# Daughter_Card_Connectors.net
KiCad netlist of a schematic drawn in Altium Designer
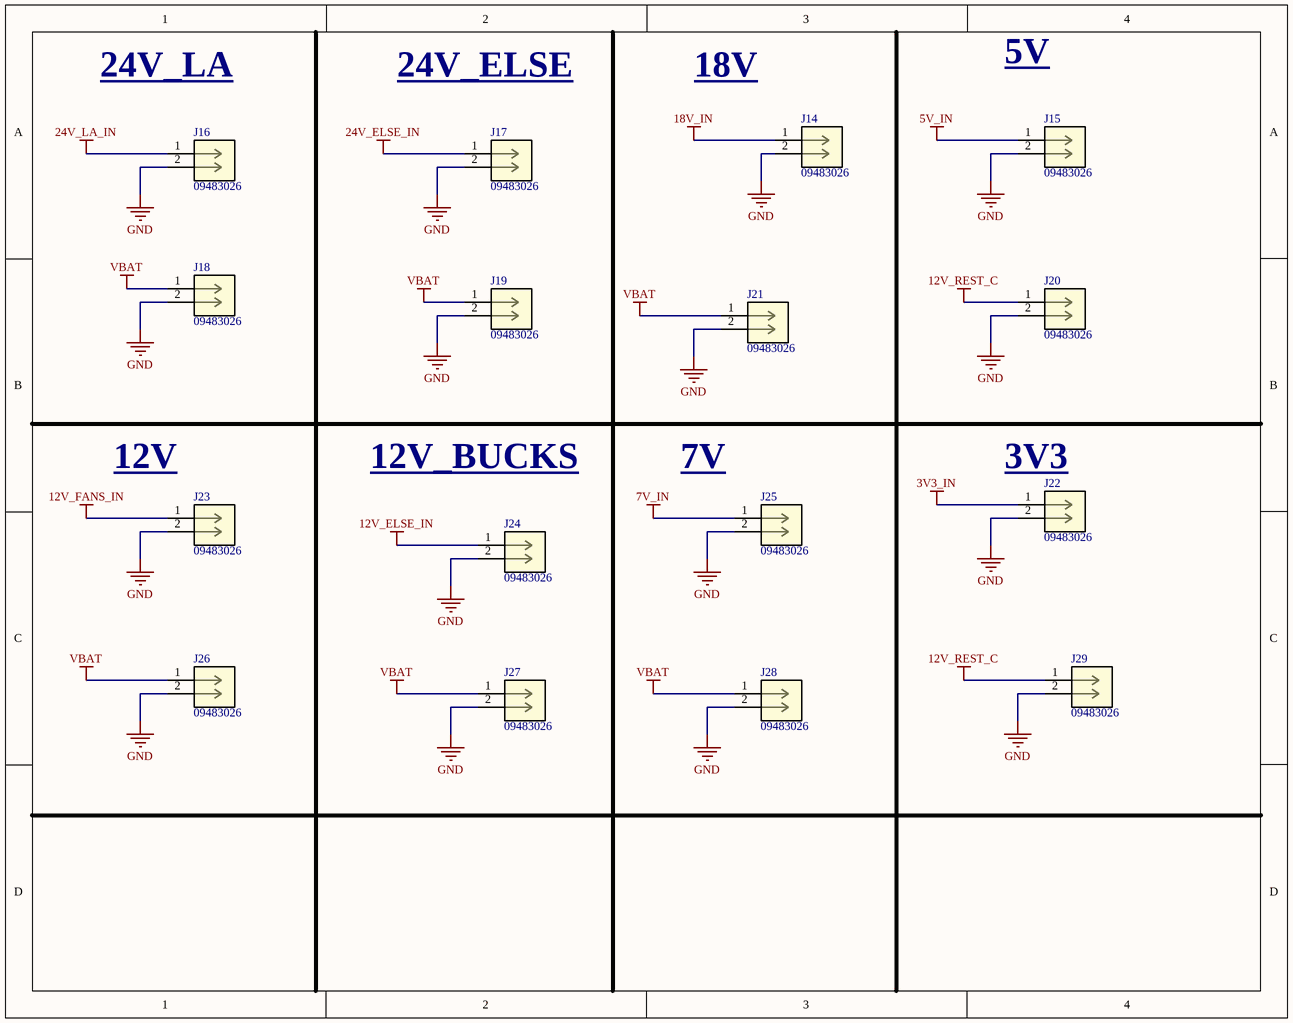
[diagram p0: Daughter_Card_Connectors.SchDoc]

(export (version "E")
  (design (tool "Eeschema 10.0.6"))
  (components
    (comp (ref "J14")
      (value "09483026")
      (footprint "CONN_SDA-41815_02_TE_H_MOL")
      (description "KK 396 PC Board Connector, Top Entry, Polyester Connector, Gold (Au) Selective, 2 Circuits")
      (fields (field (name "COPYRIGHT") "Copyright (C) 2025 Ultra Librarian. All rights reserved."))
      (libsource (lib "MasterLib") (part "CONN-2PIN-0009"))
    )
    (comp (ref "J15")
      (value "09483026")
      (footprint "CONN_SDA-41815_02_TE_H_MOL")
      (description "KK 396 PC Board Connector, Top Entry, Polyester Connector, Gold (Au) Selective, 2 Circuits")
      (fields (field (name "COPYRIGHT") "Copyright (C) 2025 Ultra Librarian. All rights reserved."))
      (libsource (lib "MasterLib") (part "CONN-2PIN-0009"))
    )
    (comp (ref "J16")
      (value "09483026")
      (footprint "CONN_SDA-41815_02_TE_H_MOL")
      (description "KK 396 PC Board Connector, Top Entry, Polyester Connector, Gold (Au) Selective, 2 Circuits")
      (fields (field (name "COPYRIGHT") "Copyright (C) 2025 Ultra Librarian. All rights reserved."))
      (libsource (lib "MasterLib") (part "CONN-2PIN-0009"))
    )
    (comp (ref "J17")
      (value "09483026")
      (footprint "CONN_SDA-41815_02_TE_H_MOL")
      (description "KK 396 PC Board Connector, Top Entry, Polyester Connector, Gold (Au) Selective, 2 Circuits")
      (fields (field (name "COPYRIGHT") "Copyright (C) 2025 Ultra Librarian. All rights reserved."))
      (libsource (lib "MasterLib") (part "CONN-2PIN-0009"))
    )
    (comp (ref "J18")
      (value "09483026")
      (footprint "CONN_SDA-41815_02_TE_H_MOL")
      (description "KK 396 PC Board Connector, Top Entry, Polyester Connector, Gold (Au) Selective, 2 Circuits")
      (fields (field (name "COPYRIGHT") "Copyright (C) 2025 Ultra Librarian. All rights reserved."))
      (libsource (lib "MasterLib") (part "CONN-2PIN-0009"))
    )
    (comp (ref "J19")
      (value "09483026")
      (footprint "CONN_SDA-41815_02_TE_H_MOL")
      (description "KK 396 PC Board Connector, Top Entry, Polyester Connector, Gold (Au) Selective, 2 Circuits")
      (fields (field (name "COPYRIGHT") "Copyright (C) 2025 Ultra Librarian. All rights reserved."))
      (libsource (lib "MasterLib") (part "CONN-2PIN-0009"))
    )
    (comp (ref "J20")
      (value "09483026")
      (footprint "CONN_SDA-41815_02_TE_H_MOL")
      (description "KK 396 PC Board Connector, Top Entry, Polyester Connector, Gold (Au) Selective, 2 Circuits")
      (fields (field (name "COPYRIGHT") "Copyright (C) 2025 Ultra Librarian. All rights reserved."))
      (libsource (lib "MasterLib") (part "CONN-2PIN-0009"))
    )
    (comp (ref "J21")
      (value "09483026")
      (footprint "CONN_SDA-41815_02_TE_H_MOL")
      (description "KK 396 PC Board Connector, Top Entry, Polyester Connector, Gold (Au) Selective, 2 Circuits")
      (fields (field (name "COPYRIGHT") "Copyright (C) 2025 Ultra Librarian. All rights reserved."))
      (libsource (lib "MasterLib") (part "CONN-2PIN-0009"))
    )
    (comp (ref "J22")
      (value "09483026")
      (footprint "CONN_SDA-41815_02_TE_H_MOL")
      (description "KK 396 PC Board Connector, Top Entry, Polyester Connector, Gold (Au) Selective, 2 Circuits")
      (fields (field (name "COPYRIGHT") "Copyright (C) 2025 Ultra Librarian. All rights reserved."))
      (libsource (lib "MasterLib") (part "CONN-2PIN-0009"))
    )
    (comp (ref "J23")
      (value "09483026")
      (footprint "CONN_SDA-41815_02_TE_H_MOL")
      (description "KK 396 PC Board Connector, Top Entry, Polyester Connector, Gold (Au) Selective, 2 Circuits")
      (fields (field (name "COPYRIGHT") "Copyright (C) 2025 Ultra Librarian. All rights reserved."))
      (libsource (lib "MasterLib") (part "CONN-2PIN-0009"))
    )
    (comp (ref "J24")
      (value "09483026")
      (footprint "CONN_SDA-41815_02_TE_H_MOL")
      (description "KK 396 PC Board Connector, Top Entry, Polyester Connector, Gold (Au) Selective, 2 Circuits")
      (fields (field (name "COPYRIGHT") "Copyright (C) 2025 Ultra Librarian. All rights reserved."))
      (libsource (lib "MasterLib") (part "CONN-2PIN-0009"))
    )
    (comp (ref "J25")
      (value "09483026")
      (footprint "CONN_SDA-41815_02_TE_H_MOL")
      (description "KK 396 PC Board Connector, Top Entry, Polyester Connector, Gold (Au) Selective, 2 Circuits")
      (fields (field (name "COPYRIGHT") "Copyright (C) 2025 Ultra Librarian. All rights reserved."))
      (libsource (lib "MasterLib") (part "CONN-2PIN-0009"))
    )
    (comp (ref "J26")
      (value "09483026")
      (footprint "CONN_SDA-41815_02_TE_H_MOL")
      (description "KK 396 PC Board Connector, Top Entry, Polyester Connector, Gold (Au) Selective, 2 Circuits")
      (fields (field (name "COPYRIGHT") "Copyright (C) 2025 Ultra Librarian. All rights reserved."))
      (libsource (lib "MasterLib") (part "CONN-2PIN-0009"))
    )
    (comp (ref "J27")
      (value "09483026")
      (footprint "CONN_SDA-41815_02_TE_H_MOL")
      (description "KK 396 PC Board Connector, Top Entry, Polyester Connector, Gold (Au) Selective, 2 Circuits")
      (fields (field (name "COPYRIGHT") "Copyright (C) 2025 Ultra Librarian. All rights reserved."))
      (libsource (lib "MasterLib") (part "CONN-2PIN-0009"))
    )
    (comp (ref "J28")
      (value "09483026")
      (footprint "CONN_SDA-41815_02_TE_H_MOL")
      (description "KK 396 PC Board Connector, Top Entry, Polyester Connector, Gold (Au) Selective, 2 Circuits")
      (fields (field (name "COPYRIGHT") "Copyright (C) 2025 Ultra Librarian. All rights reserved."))
      (libsource (lib "MasterLib") (part "CONN-2PIN-0009"))
    )
    (comp (ref "J29")
      (value "09483026")
      (footprint "CONN_SDA-41815_02_TE_H_MOL")
      (description "KK 396 PC Board Connector, Top Entry, Polyester Connector, Gold (Au) Selective, 2 Circuits")
      (fields (field (name "COPYRIGHT") "Copyright (C) 2025 Ultra Librarian. All rights reserved."))
      (libsource (lib "MasterLib") (part "CONN-2PIN-0009"))
    )
  )
  (nets
    (net (code "1") (name "3V3_IN") (class "Default")
      (node (ref "J22") (pin "1") (pinfunction "1_1") (pintype "passive"))
    )
    (net (code "2") (name "5V_IN") (class "Default")
      (node (ref "J15") (pin "1") (pinfunction "1_1") (pintype "passive"))
    )
    (net (code "3") (name "7V_IN") (class "Default")
      (node (ref "J25") (pin "1") (pinfunction "1_1") (pintype "passive"))
    )
    (net (code "4") (name "12V_ELSE_IN") (class "Default")
      (node (ref "J24") (pin "1") (pinfunction "1_1") (pintype "passive"))
    )
    (net (code "5") (name "12V_FANS_IN") (class "Default")
      (node (ref "J23") (pin "1") (pinfunction "1_1") (pintype "passive"))
    )
    (net (code "6") (name "12V_REST_C") (class "Default")
      (node (ref "J20") (pin "1") (pinfunction "1_1") (pintype "passive"))
      (node (ref "J29") (pin "1") (pinfunction "1_1") (pintype "passive"))
    )
    (net (code "7") (name "18V_IN") (class "Default")
      (node (ref "J14") (pin "1") (pinfunction "1_1") (pintype "passive"))
    )
    (net (code "8") (name "24V_ELSE_IN") (class "Default")
      (node (ref "J17") (pin "1") (pinfunction "1_1") (pintype "passive"))
    )
    (net (code "9") (name "24V_LA_IN") (class "Default")
      (node (ref "J16") (pin "1") (pinfunction "1_1") (pintype "passive"))
    )
    (net (code "10") (name "GND") (class "Default")
      (node (ref "J14") (pin "2") (pinfunction "2_2") (pintype "passive"))
      (node (ref "J15") (pin "2") (pinfunction "2_2") (pintype "passive"))
      (node (ref "J16") (pin "2") (pinfunction "2_2") (pintype "passive"))
      (node (ref "J17") (pin "2") (pinfunction "2_2") (pintype "passive"))
      (node (ref "J18") (pin "2") (pinfunction "2_2") (pintype "passive"))
      (node (ref "J19") (pin "2") (pinfunction "2_2") (pintype "passive"))
      (node (ref "J20") (pin "2") (pinfunction "2_2") (pintype "passive"))
      (node (ref "J21") (pin "2") (pinfunction "2_2") (pintype "passive"))
      (node (ref "J22") (pin "2") (pinfunction "2_2") (pintype "passive"))
      (node (ref "J23") (pin "2") (pinfunction "2_2") (pintype "passive"))
      (node (ref "J24") (pin "2") (pinfunction "2_2") (pintype "passive"))
      (node (ref "J25") (pin "2") (pinfunction "2_2") (pintype "passive"))
      (node (ref "J26") (pin "2") (pinfunction "2_2") (pintype "passive"))
      (node (ref "J27") (pin "2") (pinfunction "2_2") (pintype "passive"))
      (node (ref "J28") (pin "2") (pinfunction "2_2") (pintype "passive"))
      (node (ref "J29") (pin "2") (pinfunction "2_2") (pintype "passive"))
    )
    (net (code "11") (name "VBAT") (class "Default")
      (node (ref "J18") (pin "1") (pinfunction "1_1") (pintype "passive"))
      (node (ref "J19") (pin "1") (pinfunction "1_1") (pintype "passive"))
      (node (ref "J21") (pin "1") (pinfunction "1_1") (pintype "passive"))
      (node (ref "J26") (pin "1") (pinfunction "1_1") (pintype "passive"))
      (node (ref "J27") (pin "1") (pinfunction "1_1") (pintype "passive"))
      (node (ref "J28") (pin "1") (pinfunction "1_1") (pintype "passive"))
    )
  )
)
